# Sensor_PCB.net
KiCad netlist of a schematic drawn in EAGLE
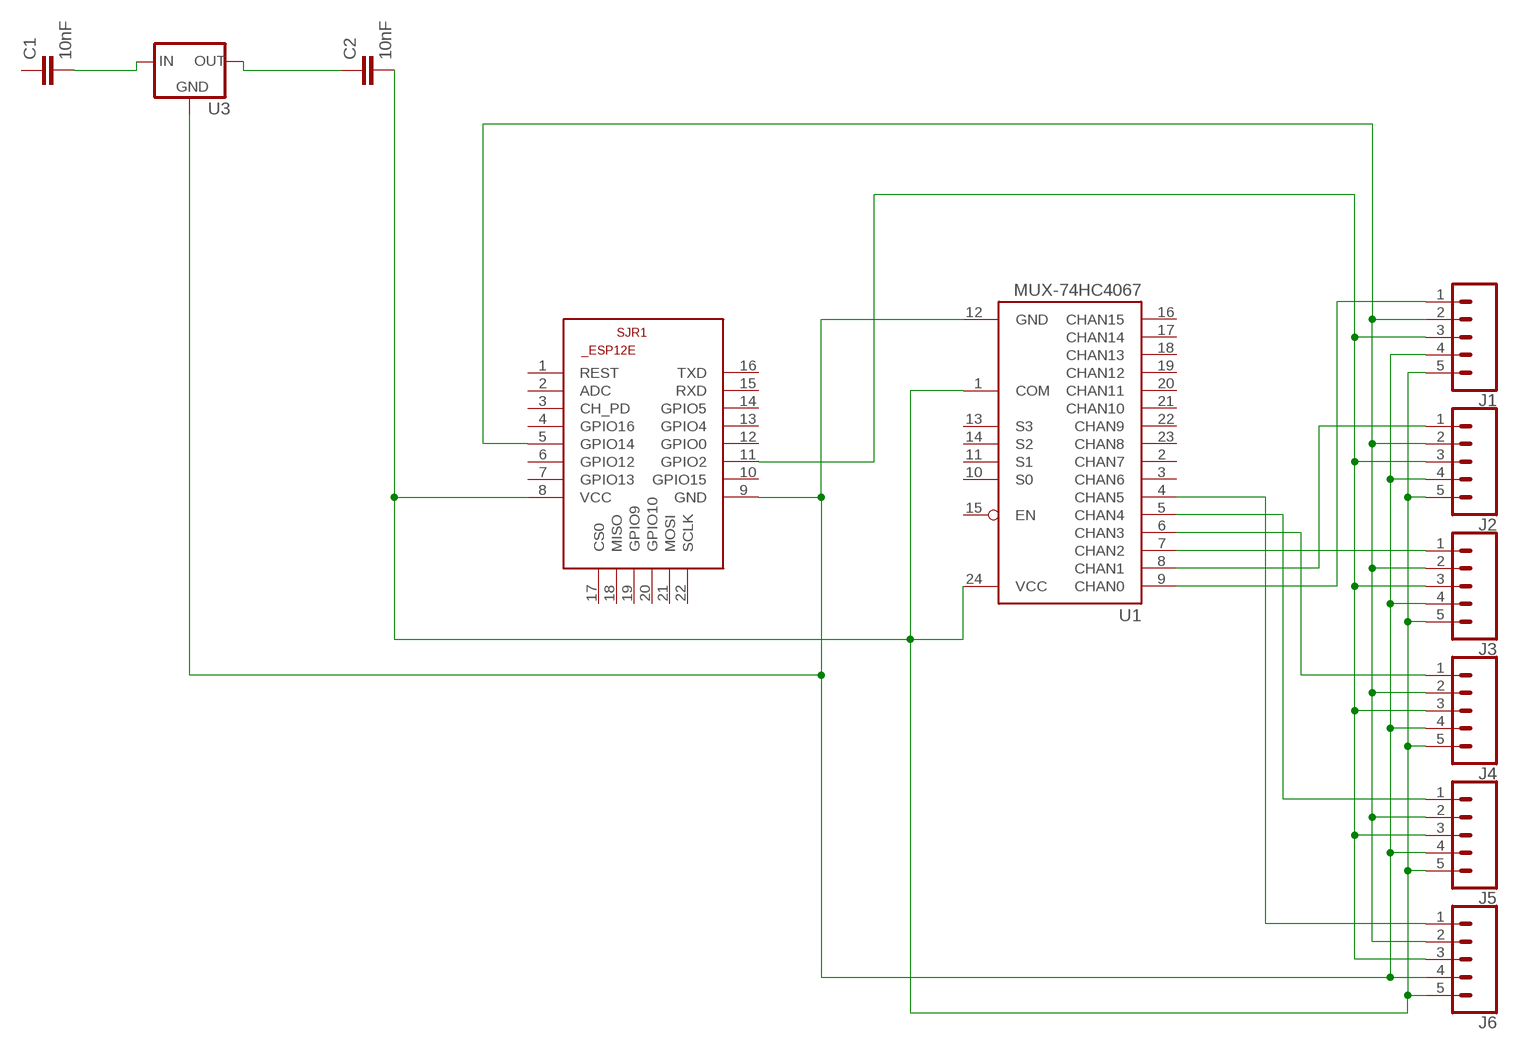
[diagram p0: schematic, sheet 1]

(export (version "E")
  (design (tool "Eeschema 10.0.6"))
  (components
    (comp (ref "C1")
      (value "10nF")
      (footprint "eagle-import:0603")
      (libsource (lib "eagle-import") (part "10NF-0603-50V-10%"))
    )
    (comp (ref "C2")
      (value "10nF")
      (footprint "eagle-import:0603")
      (libsource (lib "eagle-import") (part "10NF-0603-50V-10%"))
    )
    (comp (ref "J1")
      (value "CONN_05JST-VERT")
      (footprint "eagle-import:JST-5-PTH-VERT")
      (libsource (lib "eagle-import") (part "CONN_05JST-VERT"))
    )
    (comp (ref "J2")
      (value "CONN_05JST-VERT")
      (footprint "eagle-import:JST-5-PTH-VERT")
      (libsource (lib "eagle-import") (part "CONN_05JST-VERT"))
    )
    (comp (ref "J3")
      (value "CONN_05JST-VERT")
      (footprint "eagle-import:JST-5-PTH-VERT")
      (libsource (lib "eagle-import") (part "CONN_05JST-VERT"))
    )
    (comp (ref "J4")
      (value "CONN_05JST-VERT")
      (footprint "eagle-import:JST-5-PTH-VERT")
      (libsource (lib "eagle-import") (part "CONN_05JST-VERT"))
    )
    (comp (ref "J5")
      (value "CONN_05JST-VERT")
      (footprint "eagle-import:JST-5-PTH-VERT")
      (libsource (lib "eagle-import") (part "CONN_05JST-VERT"))
    )
    (comp (ref "J6")
      (value "CONN_05JST-VERT")
      (footprint "eagle-import:JST-5-PTH-VERT")
      (libsource (lib "eagle-import") (part "CONN_05JST-VERT"))
    )
    (comp (ref "SJR1")
      (value "ESP8266-12EESP12E")
      (footprint "eagle-import:ESP8266-ESP12E")
      (libsource (lib "eagle-import") (part "ESP8266-12EESP12E"))
    )
    (comp (ref "U1")
      (value "MUX-74HC4067")
      (footprint "eagle-import:SSOP24")
      (libsource (lib "eagle-import") (part "MUX-74HC4067SMD"))
    )
    (comp (ref "U3")
      (value "V_REG_78XX-TO-220")
      (footprint "eagle-import:TO-220-ALT")
      (libsource (lib "eagle-import") (part "V_REG_78XX-TO-220"))
    )
  )
  (nets
    (net (code "1") (name "Net-(C1-Pad2)") (class "Default")
      (node (ref "C1") (pin "2") (pinfunction "2_2") (pintype "passive"))
      (node (ref "U3") (pin "IN") (pinfunction "IN_IN") (pintype "input"))
    )
    (net (code "2") (name "Net-(C2-Pad1)") (class "Default")
      (node (ref "C2") (pin "1") (pinfunction "1_1") (pintype "passive"))
      (node (ref "U3") (pin "OUT") (pinfunction "OUT_OUT") (pintype "passive"))
    )
    (net (code "3") (name "Net-(SJR1-GND)") (class "Default")
      (node (ref "J1") (pin "4") (pinfunction "4_4") (pintype "passive"))
      (node (ref "J2") (pin "4") (pinfunction "4_4") (pintype "passive"))
      (node (ref "J3") (pin "4") (pinfunction "4_4") (pintype "passive"))
      (node (ref "J4") (pin "4") (pinfunction "4_4") (pintype "passive"))
      (node (ref "J5") (pin "4") (pinfunction "4_4") (pintype "passive"))
      (node (ref "J6") (pin "4") (pinfunction "4_4") (pintype "passive"))
      (node (ref "SJR1") (pin "9") (pinfunction "GND_9") (pintype "bidirectional"))
      (node (ref "U1") (pin "12") (pinfunction "GND_12") (pintype "bidirectional"))
      (node (ref "U3") (pin "GND") (pinfunction "GND_GND") (pintype "input"))
    )
    (net (code "4") (name "Net-(SJR1-GPIO2)") (class "Default")
      (node (ref "J1") (pin "3") (pinfunction "3_3") (pintype "passive"))
      (node (ref "J2") (pin "3") (pinfunction "3_3") (pintype "passive"))
      (node (ref "J3") (pin "3") (pinfunction "3_3") (pintype "passive"))
      (node (ref "J4") (pin "3") (pinfunction "3_3") (pintype "passive"))
      (node (ref "J5") (pin "3") (pinfunction "3_3") (pintype "passive"))
      (node (ref "J6") (pin "3") (pinfunction "3_3") (pintype "passive"))
      (node (ref "SJR1") (pin "11") (pinfunction "GPIO2_11") (pintype "bidirectional"))
    )
    (net (code "5") (name "Net-(SJR1-GPIO14)") (class "Default")
      (node (ref "J1") (pin "2") (pinfunction "2_2") (pintype "passive"))
      (node (ref "J2") (pin "2") (pinfunction "2_2") (pintype "passive"))
      (node (ref "J3") (pin "2") (pinfunction "2_2") (pintype "passive"))
      (node (ref "J4") (pin "2") (pinfunction "2_2") (pintype "passive"))
      (node (ref "J5") (pin "2") (pinfunction "2_2") (pintype "passive"))
      (node (ref "J6") (pin "2") (pinfunction "2_2") (pintype "passive"))
      (node (ref "SJR1") (pin "5") (pinfunction "GPIO14_5") (pintype "bidirectional"))
    )
    (net (code "6") (name "Net-(SJR1-VCC)") (class "Default")
      (node (ref "C2") (pin "2") (pinfunction "2_2") (pintype "passive"))
      (node (ref "J1") (pin "5") (pinfunction "5_5") (pintype "passive"))
      (node (ref "J2") (pin "5") (pinfunction "5_5") (pintype "passive"))
      (node (ref "J3") (pin "5") (pinfunction "5_5") (pintype "passive"))
      (node (ref "J4") (pin "5") (pinfunction "5_5") (pintype "passive"))
      (node (ref "J5") (pin "5") (pinfunction "5_5") (pintype "passive"))
      (node (ref "J6") (pin "5") (pinfunction "5_5") (pintype "passive"))
      (node (ref "SJR1") (pin "8") (pinfunction "VCC_8") (pintype "bidirectional"))
      (node (ref "U1") (pin "1") (pinfunction "COM_1") (pintype "bidirectional"))
      (node (ref "U1") (pin "24") (pinfunction "VCC_24") (pintype "bidirectional"))
    )
    (net (code "7") (name "Net-(U1-CHAN0)") (class "Default")
      (node (ref "J1") (pin "1") (pinfunction "1_1") (pintype "passive"))
      (node (ref "U1") (pin "9") (pinfunction "CHAN0_9") (pintype "bidirectional"))
    )
    (net (code "8") (name "Net-(U1-CHAN1)") (class "Default")
      (node (ref "J2") (pin "1") (pinfunction "1_1") (pintype "passive"))
      (node (ref "U1") (pin "8") (pinfunction "CHAN1_8") (pintype "bidirectional"))
    )
    (net (code "9") (name "Net-(U1-CHAN2)") (class "Default")
      (node (ref "J3") (pin "1") (pinfunction "1_1") (pintype "passive"))
      (node (ref "U1") (pin "7") (pinfunction "CHAN2_7") (pintype "bidirectional"))
    )
    (net (code "10") (name "Net-(U1-CHAN3)") (class "Default")
      (node (ref "J4") (pin "1") (pinfunction "1_1") (pintype "passive"))
      (node (ref "U1") (pin "6") (pinfunction "CHAN3_6") (pintype "bidirectional"))
    )
    (net (code "11") (name "Net-(U1-CHAN4)") (class "Default")
      (node (ref "J5") (pin "1") (pinfunction "1_1") (pintype "passive"))
      (node (ref "U1") (pin "5") (pinfunction "CHAN4_5") (pintype "bidirectional"))
    )
    (net (code "12") (name "Net-(U1-CHAN5)") (class "Default")
      (node (ref "J6") (pin "1") (pinfunction "1_1") (pintype "passive"))
      (node (ref "U1") (pin "4") (pinfunction "CHAN5_4") (pintype "bidirectional"))
    )
    (net (code "13") (name "unconnected-(C1-Pad1)") (class "Default")
      (node (ref "C1") (pin "1") (pinfunction "1_1") (pintype "passive"))
    )
    (net (code "14") (name "unconnected-(SJR1-ADC-Pad2)") (class "Default")
      (node (ref "SJR1") (pin "2") (pinfunction "ADC_2") (pintype "bidirectional"))
    )
    (net (code "15") (name "unconnected-(SJR1-CH_PD-Pad3)") (class "Default")
      (node (ref "SJR1") (pin "3") (pinfunction "CH_PD_3") (pintype "bidirectional"))
    )
    (net (code "16") (name "unconnected-(SJR1-CS0-Pad17)") (class "Default")
      (node (ref "SJR1") (pin "17") (pinfunction "CS0_17") (pintype "bidirectional"))
    )
    (net (code "17") (name "unconnected-(SJR1-GPIO0-Pad12)") (class "Default")
      (node (ref "SJR1") (pin "12") (pinfunction "GPIO0_12") (pintype "bidirectional"))
    )
    (net (code "18") (name "unconnected-(SJR1-GPIO4-Pad13)") (class "Default")
      (node (ref "SJR1") (pin "13") (pinfunction "GPIO4_13") (pintype "bidirectional"))
    )
    (net (code "19") (name "unconnected-(SJR1-GPIO5-Pad14)") (class "Default")
      (node (ref "SJR1") (pin "14") (pinfunction "GPIO5_14") (pintype "bidirectional"))
    )
    (net (code "20") (name "unconnected-(SJR1-GPIO9-Pad19)") (class "Default")
      (node (ref "SJR1") (pin "19") (pinfunction "GPIO9_19") (pintype "bidirectional"))
    )
    (net (code "21") (name "unconnected-(SJR1-GPIO10-Pad20)") (class "Default")
      (node (ref "SJR1") (pin "20") (pinfunction "GPIO10_20") (pintype "bidirectional"))
    )
    (net (code "22") (name "unconnected-(SJR1-GPIO12-Pad6)") (class "Default")
      (node (ref "SJR1") (pin "6") (pinfunction "GPIO12_6") (pintype "bidirectional"))
    )
    (net (code "23") (name "unconnected-(SJR1-GPIO13-Pad7)") (class "Default")
      (node (ref "SJR1") (pin "7") (pinfunction "GPIO13_7") (pintype "bidirectional"))
    )
    (net (code "24") (name "unconnected-(SJR1-GPIO15-Pad10)") (class "Default")
      (node (ref "SJR1") (pin "10") (pinfunction "GPIO15_10") (pintype "bidirectional"))
    )
    (net (code "25") (name "unconnected-(SJR1-GPIO16-Pad4)") (class "Default")
      (node (ref "SJR1") (pin "4") (pinfunction "GPIO16_4") (pintype "bidirectional"))
    )
    (net (code "26") (name "unconnected-(SJR1-MISO-Pad18)") (class "Default")
      (node (ref "SJR1") (pin "18") (pinfunction "MISO_18") (pintype "bidirectional"))
    )
    (net (code "27") (name "unconnected-(SJR1-MOSI-Pad21)") (class "Default")
      (node (ref "SJR1") (pin "21") (pinfunction "MOSI_21") (pintype "bidirectional"))
    )
    (net (code "28") (name "unconnected-(SJR1-REST-Pad1)") (class "Default")
      (node (ref "SJR1") (pin "1") (pinfunction "REST_1") (pintype "bidirectional"))
    )
    (net (code "29") (name "unconnected-(SJR1-RXD-Pad15)") (class "Default")
      (node (ref "SJR1") (pin "15") (pinfunction "RXD_15") (pintype "bidirectional"))
    )
    (net (code "30") (name "unconnected-(SJR1-SCLK-Pad22)") (class "Default")
      (node (ref "SJR1") (pin "22") (pinfunction "SCLK_22") (pintype "bidirectional"))
    )
    (net (code "31") (name "unconnected-(SJR1-TXD-Pad16)") (class "Default")
      (node (ref "SJR1") (pin "16") (pinfunction "TXD_16") (pintype "bidirectional"))
    )
    (net (code "32") (name "unconnected-(U1-CHAN6-Pad3)") (class "Default")
      (node (ref "U1") (pin "3") (pinfunction "CHAN6_3") (pintype "bidirectional"))
    )
    (net (code "33") (name "unconnected-(U1-CHAN7-Pad2)") (class "Default")
      (node (ref "U1") (pin "2") (pinfunction "CHAN7_2") (pintype "bidirectional"))
    )
    (net (code "34") (name "unconnected-(U1-CHAN8-Pad23)") (class "Default")
      (node (ref "U1") (pin "23") (pinfunction "CHAN8_23") (pintype "bidirectional"))
    )
    (net (code "35") (name "unconnected-(U1-CHAN9-Pad22)") (class "Default")
      (node (ref "U1") (pin "22") (pinfunction "CHAN9_22") (pintype "bidirectional"))
    )
    (net (code "36") (name "unconnected-(U1-CHAN10-Pad21)") (class "Default")
      (node (ref "U1") (pin "21") (pinfunction "CHAN10_21") (pintype "bidirectional"))
    )
    (net (code "37") (name "unconnected-(U1-CHAN11-Pad20)") (class "Default")
      (node (ref "U1") (pin "20") (pinfunction "CHAN11_20") (pintype "bidirectional"))
    )
    (net (code "38") (name "unconnected-(U1-CHAN12-Pad19)") (class "Default")
      (node (ref "U1") (pin "19") (pinfunction "CHAN12_19") (pintype "bidirectional"))
    )
    (net (code "39") (name "unconnected-(U1-CHAN13-Pad18)") (class "Default")
      (node (ref "U1") (pin "18") (pinfunction "CHAN13_18") (pintype "bidirectional"))
    )
    (net (code "40") (name "unconnected-(U1-CHAN14-Pad17)") (class "Default")
      (node (ref "U1") (pin "17") (pinfunction "CHAN14_17") (pintype "bidirectional"))
    )
    (net (code "41") (name "unconnected-(U1-CHAN15-Pad16)") (class "Default")
      (node (ref "U1") (pin "16") (pinfunction "CHAN15_16") (pintype "bidirectional"))
    )
    (net (code "42") (name "unconnected-(U1-EN-Pad15)") (class "Default")
      (node (ref "U1") (pin "15") (pinfunction "EN_15") (pintype "input"))
    )
    (net (code "43") (name "unconnected-(U1-S0-Pad10)") (class "Default")
      (node (ref "U1") (pin "10") (pinfunction "S0_10") (pintype "input"))
    )
    (net (code "44") (name "unconnected-(U1-S1-Pad11)") (class "Default")
      (node (ref "U1") (pin "11") (pinfunction "S1_11") (pintype "input"))
    )
    (net (code "45") (name "unconnected-(U1-S2-Pad14)") (class "Default")
      (node (ref "U1") (pin "14") (pinfunction "S2_14") (pintype "input"))
    )
    (net (code "46") (name "unconnected-(U1-S3-Pad13)") (class "Default")
      (node (ref "U1") (pin "13") (pinfunction "S3_13") (pintype "input"))
    )
  )
)
